# Frontboard_Rev1.net
KiCad netlist of a schematic drawn in EAGLE
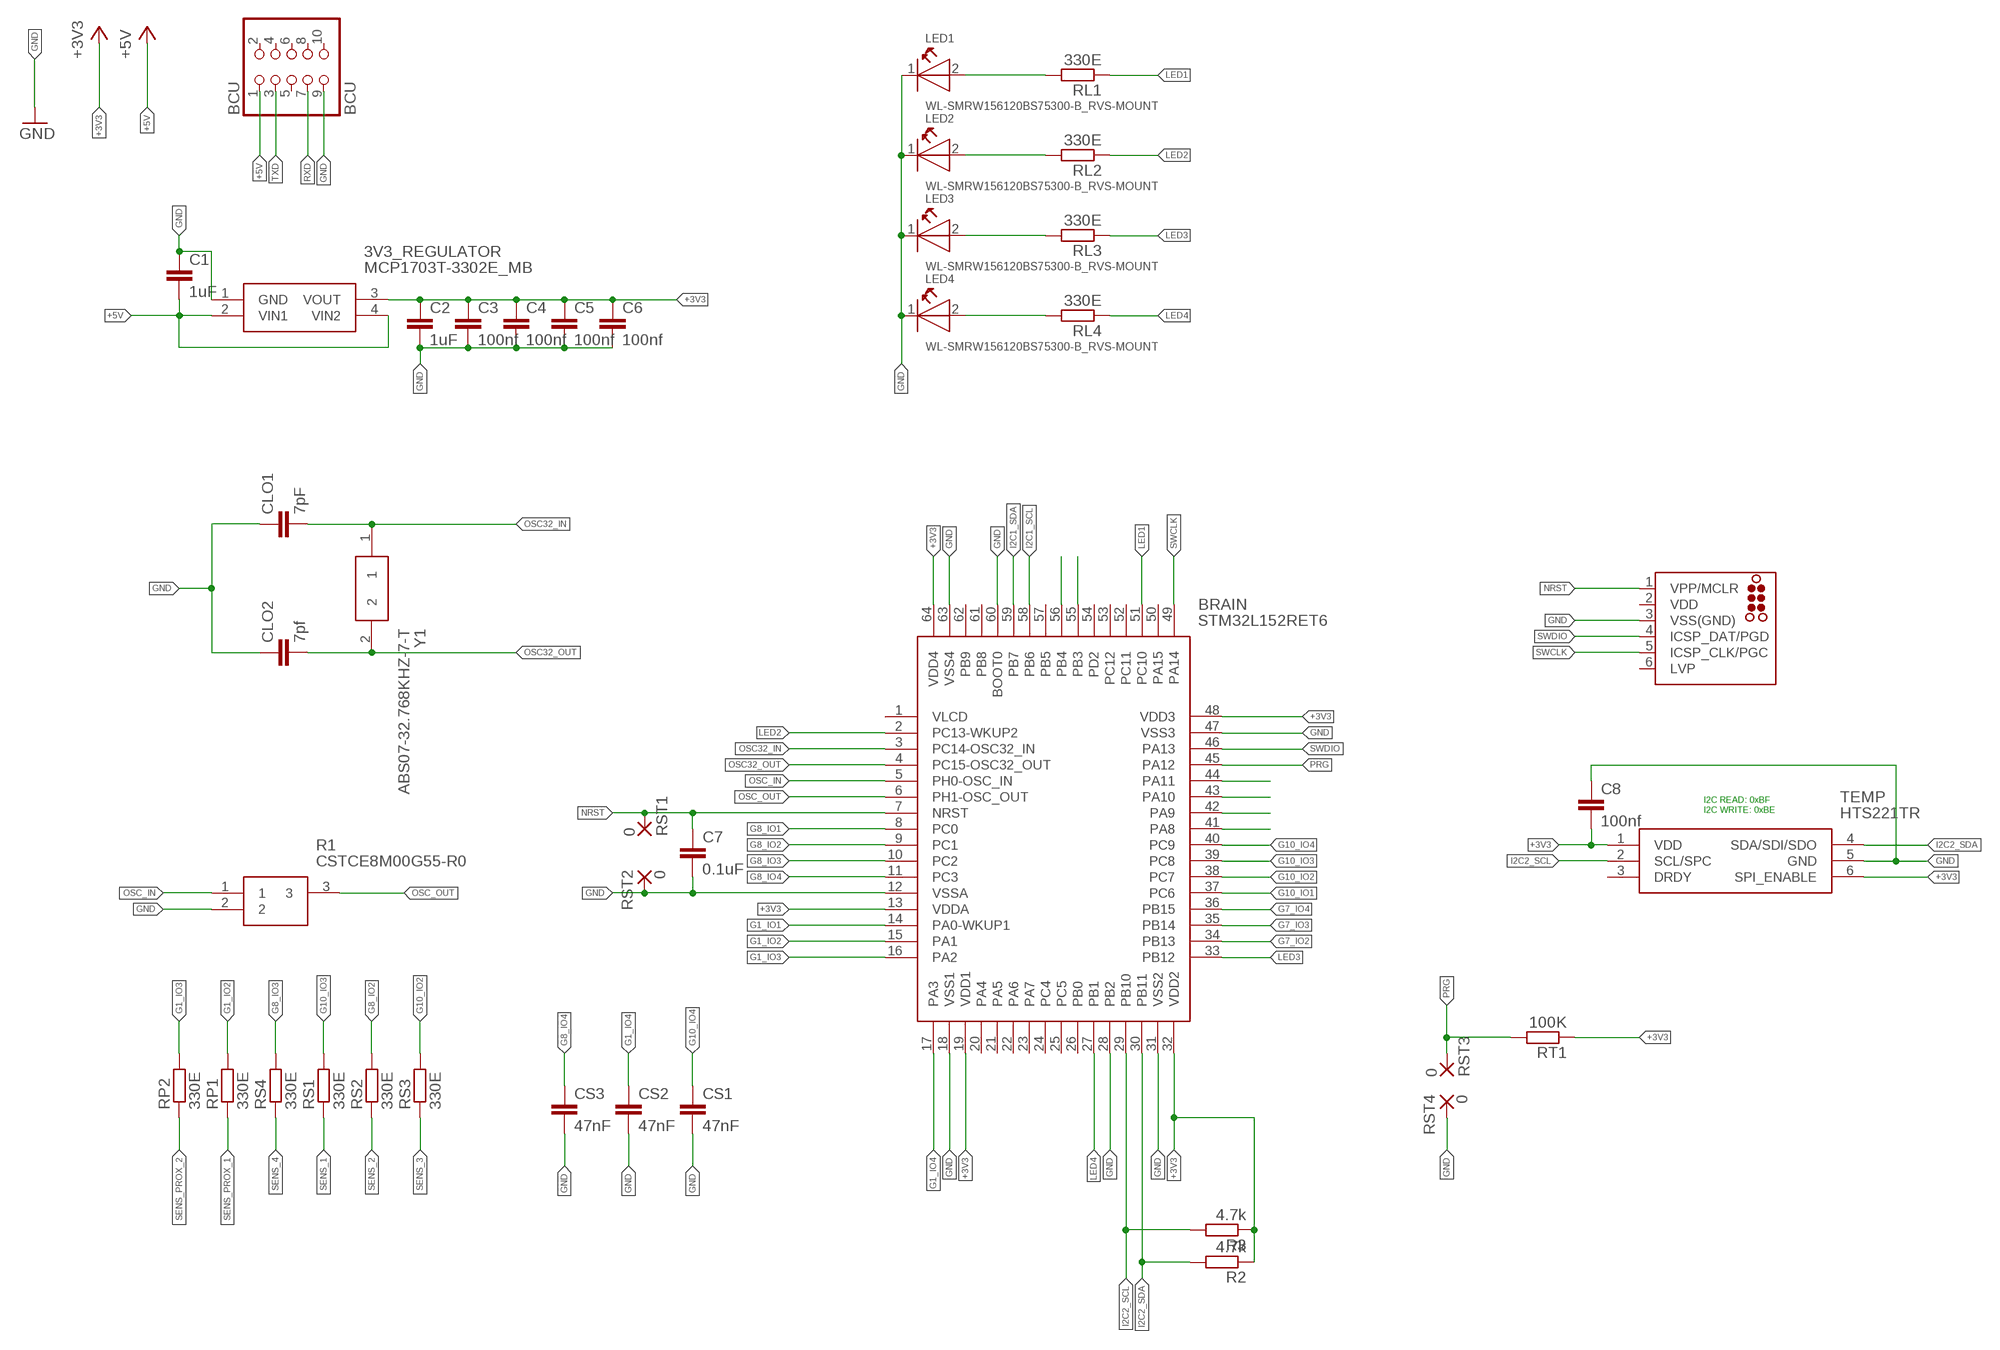
[diagram p0: schematic, sheet 1]

(export (version "E")
  (design (tool "Eeschema 10.0.6"))
  (components
    (comp (ref "3V3_REGULATOR")
      (value "MCP1703T-3302E_MB")
      (footprint "eagle-import:SOT-89(MB)")
      (fields
        (field (name "ARROW_PART_NUMBER") "MCP1703T-3302E/MB")
        (field (name "RS_PART_NUMBER") "9122916")
      )
      (libsource (lib "eagle-import") (part "MCP1703T-3302E_MB"))
    )
    (comp (ref "BCU")
      (value "BCU")
      (footprint "eagle-import:2X05SMD")
      (libsource (lib "eagle-import") (part "PINHD-2X5_2.54-SMD"))
    )
    (comp (ref "BRAIN")
      (value "STM32L152RET6")
      (footprint "eagle-import:QFP50P1200X1200X160-64N")
      (libsource (lib "eagle-import") (part "STM32L152RET6"))
    )
    (comp (ref "C1")
      (value "1uF")
      (footprint "eagle-import:C0603")
      (libsource (lib "eagle-import") (part "C-EUC0603"))
    )
    (comp (ref "C2")
      (value "1uF")
      (footprint "eagle-import:C0603")
      (libsource (lib "eagle-import") (part "C-EUC0603"))
    )
    (comp (ref "C3")
      (value "100nf")
      (footprint "eagle-import:C0603")
      (libsource (lib "eagle-import") (part "C-EUC0603"))
    )
    (comp (ref "C4")
      (value "100nf")
      (footprint "eagle-import:C0603")
      (libsource (lib "eagle-import") (part "C-EUC0603"))
    )
    (comp (ref "C5")
      (value "100nf")
      (footprint "eagle-import:C0603")
      (libsource (lib "eagle-import") (part "C-EUC0603"))
    )
    (comp (ref "C6")
      (value "100nf")
      (footprint "eagle-import:C0603")
      (libsource (lib "eagle-import") (part "C-EUC0603"))
    )
    (comp (ref "C7")
      (value "0.1uF")
      (footprint "eagle-import:C0603")
      (libsource (lib "eagle-import") (part "C-EUC0603"))
    )
    (comp (ref "C8")
      (value "100nf")
      (footprint "eagle-import:C0603")
      (libsource (lib "eagle-import") (part "C-EUC0603"))
    )
    (comp (ref "CLO1")
      (value "7pF")
      (footprint "eagle-import:C0603")
      (libsource (lib "eagle-import") (part "C-EUC0603"))
    )
    (comp (ref "CLO2")
      (value "7pf")
      (footprint "eagle-import:C0603")
      (libsource (lib "eagle-import") (part "C-EUC0603"))
    )
    (comp (ref "CS1")
      (value "47nF")
      (footprint "eagle-import:C0603")
      (libsource (lib "eagle-import") (part "C-EUC0603"))
    )
    (comp (ref "CS2")
      (value "47nF")
      (footprint "eagle-import:C0603")
      (libsource (lib "eagle-import") (part "C-EUC0603"))
    )
    (comp (ref "CS3")
      (value "47nF")
      (footprint "eagle-import:C0603")
      (libsource (lib "eagle-import") (part "C-EUC0603"))
    )
    (comp (ref "LED1")
      (value "WL-SMRW156120BS75300-B_RVS-MOUNT")
      (footprint "eagle-import:WL-SMRW-1206-CYLDR-REVERSE-MOUNT")
      (libsource (lib "eagle-import") (part "WL-SMRW156120BS75300-B_RVS-MOUNT"))
    )
    (comp (ref "LED2")
      (value "WL-SMRW156120BS75300-B_RVS-MOUNT")
      (footprint "eagle-import:WL-SMRW-1206-CYLDR-REVERSE-MOUNT")
      (libsource (lib "eagle-import") (part "WL-SMRW156120BS75300-B_RVS-MOUNT"))
    )
    (comp (ref "LED3")
      (value "WL-SMRW156120BS75300-B_RVS-MOUNT")
      (footprint "eagle-import:WL-SMRW-1206-CYLDR-REVERSE-MOUNT")
      (libsource (lib "eagle-import") (part "WL-SMRW156120BS75300-B_RVS-MOUNT"))
    )
    (comp (ref "LED4")
      (value "WL-SMRW156120BS75300-B_RVS-MOUNT")
      (footprint "eagle-import:WL-SMRW-1206-CYLDR-REVERSE-MOUNT")
      (libsource (lib "eagle-import") (part "WL-SMRW156120BS75300-B_RVS-MOUNT"))
    )
    (comp (ref "R1")
      (value "CSTCE8M00G55-R0")
      (footprint "eagle-import:CSTCE12M0G55-R0")
      (fields (field (name "RS_PART_NUMBER") "7214821P"))
      (libsource (lib "eagle-import") (part "CSTCE8M00G55-R0"))
    )
    (comp (ref "R2")
      (value "4.7k")
      (footprint "eagle-import:R0603")
      (libsource (lib "eagle-import") (part "R-EU_R0603"))
    )
    (comp (ref "R3")
      (value "4.7k")
      (footprint "eagle-import:R0603")
      (libsource (lib "eagle-import") (part "R-EU_R0603"))
    )
    (comp (ref "RL1")
      (value "330E")
      (footprint "eagle-import:R0603")
      (libsource (lib "eagle-import") (part "R-EU_R0603"))
    )
    (comp (ref "RL2")
      (value "330E")
      (footprint "eagle-import:R0603")
      (libsource (lib "eagle-import") (part "R-EU_R0603"))
    )
    (comp (ref "RL3")
      (value "330E")
      (footprint "eagle-import:R0603")
      (libsource (lib "eagle-import") (part "R-EU_R0603"))
    )
    (comp (ref "RL4")
      (value "330E")
      (footprint "eagle-import:R0603")
      (libsource (lib "eagle-import") (part "R-EU_R0603"))
    )
    (comp (ref "RP1")
      (value "330E")
      (footprint "eagle-import:R0603")
      (libsource (lib "eagle-import") (part "R-EU_R0603"))
    )
    (comp (ref "RP2")
      (value "330E")
      (footprint "eagle-import:R0603")
      (libsource (lib "eagle-import") (part "R-EU_R0603"))
    )
    (comp (ref "RS1")
      (value "330E")
      (footprint "eagle-import:R0603")
      (libsource (lib "eagle-import") (part "R-EU_R0603"))
    )
    (comp (ref "RS2")
      (value "330E")
      (footprint "eagle-import:R0603")
      (libsource (lib "eagle-import") (part "R-EU_R0603"))
    )
    (comp (ref "RS3")
      (value "330E")
      (footprint "eagle-import:R0603")
      (libsource (lib "eagle-import") (part "R-EU_R0603"))
    )
    (comp (ref "RS4")
      (value "330E")
      (footprint "eagle-import:R0603")
      (libsource (lib "eagle-import") (part "R-EU_R0603"))
    )
    (comp (ref "RST1")
      (value "0")
      (footprint "eagle-import:SMD2,54-5,08")
      (libsource (lib "eagle-import") (part "SMD5"))
    )
    (comp (ref "RST2")
      (value "0")
      (footprint "eagle-import:SMD2,54-5,08")
      (libsource (lib "eagle-import") (part "SMD5"))
    )
    (comp (ref "RST3")
      (value "0")
      (footprint "eagle-import:SMD2,54-5,08")
      (libsource (lib "eagle-import") (part "SMD5"))
    )
    (comp (ref "RST4")
      (value "0")
      (footprint "eagle-import:SMD2,54-5,08")
      (libsource (lib "eagle-import") (part "SMD5"))
    )
    (comp (ref "RT1")
      (value "100K")
      (footprint "eagle-import:R0603")
      (libsource (lib "eagle-import") (part "R-EU_R0603"))
    )
    (comp (ref "SWD")
      (value "SWD")
      (footprint "eagle-import:TC2030-MCP-NL")
      (libsource (lib "eagle-import") (part "TC2030-MCP-NL"))
    )
    (comp (ref "TEMP")
      (value "HTS221TR")
      (footprint "eagle-import:HLGA-6L")
      (fields (field (name "RS_PART_NUMBER") "1660935"))
      (libsource (lib "eagle-import") (part "HTS221TR"))
    )
    (comp (ref "Y1")
      (value "ABS07-32.768KHZ-7-T")
      (footprint "eagle-import:ABS-07")
      (fields (field (name "RS_PART_NUMBER") "1712773P"))
      (libsource (lib "eagle-import") (part "ABS07-32.768KHZ-7-T"))
    )
  )
  (nets
    (net (code "1") (name "+3V3") (class "Default")
      (node (ref "3V3_REGULATOR") (pin "3") (pinfunction "VOUT_3") (pintype "bidirectional"))
      (node (ref "BRAIN") (pin "13") (pinfunction "VDDA_13") (pintype "power_in"))
      (node (ref "BRAIN") (pin "19") (pinfunction "VDD1_19") (pintype "power_in"))
      (node (ref "BRAIN") (pin "32") (pinfunction "VDD2_32") (pintype "power_in"))
      (node (ref "BRAIN") (pin "48") (pinfunction "VDD3_48") (pintype "power_in"))
      (node (ref "BRAIN") (pin "64") (pinfunction "VDD4_64") (pintype "power_in"))
      (node (ref "C2") (pin "1") (pinfunction "1_1") (pintype "passive"))
      (node (ref "C3") (pin "1") (pinfunction "1_1") (pintype "passive"))
      (node (ref "C4") (pin "1") (pinfunction "1_1") (pintype "passive"))
      (node (ref "C5") (pin "1") (pinfunction "1_1") (pintype "passive"))
      (node (ref "C6") (pin "1") (pinfunction "1_1") (pintype "passive"))
      (node (ref "C8") (pin "2") (pinfunction "2_2") (pintype "passive"))
      (node (ref "R2") (pin "1") (pinfunction "1_1") (pintype "passive"))
      (node (ref "R3") (pin "1") (pinfunction "1_1") (pintype "passive"))
      (node (ref "RT1") (pin "1") (pinfunction "1_1") (pintype "passive"))
      (node (ref "TEMP") (pin "1") (pinfunction "VDD_1") (pintype "bidirectional"))
      (node (ref "TEMP") (pin "6") (pinfunction "SPI_ENABLE_6") (pintype "bidirectional"))
    )
    (net (code "2") (name "+5V") (class "Default")
      (node (ref "3V3_REGULATOR") (pin "2") (pinfunction "VIN1_2") (pintype "bidirectional"))
      (node (ref "3V3_REGULATOR") (pin "4") (pinfunction "VIN2_4") (pintype "bidirectional"))
      (node (ref "BCU") (pin "1") (pinfunction "1_1") (pintype "passive"))
      (node (ref "C1") (pin "2") (pinfunction "2_2") (pintype "passive"))
    )
    (net (code "3") (name "/VDD") (class "Default")
      (node (ref "SWD") (pin "2") (pinfunction "VDD_2") (pintype "power_in"))
    )
    (net (code "4") (name "/VLCD") (class "Default")
      (node (ref "BRAIN") (pin "1") (pinfunction "VLCD_1") (pintype "power_in"))
    )
    (net (code "5") (name "G1_IO1") (class "Default")
      (node (ref "BRAIN") (pin "14") (pinfunction "PA0-WKUP1_14") (pintype "bidirectional"))
    )
    (net (code "6") (name "G1_IO2") (class "Default")
      (node (ref "BRAIN") (pin "15") (pinfunction "PA1_15") (pintype "bidirectional"))
      (node (ref "RP1") (pin "2") (pinfunction "2_2") (pintype "passive"))
    )
    (net (code "7") (name "G1_IO3") (class "Default")
      (node (ref "BRAIN") (pin "16") (pinfunction "PA2_16") (pintype "bidirectional"))
      (node (ref "RP2") (pin "2") (pinfunction "2_2") (pintype "passive"))
    )
    (net (code "8") (name "G1_IO4") (class "Default")
      (node (ref "BRAIN") (pin "17") (pinfunction "PA3_17") (pintype "bidirectional"))
      (node (ref "CS2") (pin "1") (pinfunction "1_1") (pintype "passive"))
    )
    (net (code "9") (name "G7_IO2") (class "Default")
      (node (ref "BRAIN") (pin "34") (pinfunction "PB13_34") (pintype "bidirectional"))
    )
    (net (code "10") (name "G7_IO3") (class "Default")
      (node (ref "BRAIN") (pin "35") (pinfunction "PB14_35") (pintype "bidirectional"))
    )
    (net (code "11") (name "G7_IO4") (class "Default")
      (node (ref "BRAIN") (pin "36") (pinfunction "PB15_36") (pintype "bidirectional"))
    )
    (net (code "12") (name "G8_IO1") (class "Default")
      (node (ref "BRAIN") (pin "8") (pinfunction "PC0_8") (pintype "bidirectional"))
    )
    (net (code "13") (name "G8_IO2") (class "Default")
      (node (ref "BRAIN") (pin "9") (pinfunction "PC1_9") (pintype "bidirectional"))
      (node (ref "RS2") (pin "2") (pinfunction "2_2") (pintype "passive"))
    )
    (net (code "14") (name "G8_IO3") (class "Default")
      (node (ref "BRAIN") (pin "10") (pinfunction "PC2_10") (pintype "bidirectional"))
      (node (ref "RS4") (pin "2") (pinfunction "2_2") (pintype "passive"))
    )
    (net (code "15") (name "G8_IO4") (class "Default")
      (node (ref "BRAIN") (pin "11") (pinfunction "PC3_11") (pintype "bidirectional"))
      (node (ref "CS3") (pin "1") (pinfunction "1_1") (pintype "passive"))
    )
    (net (code "16") (name "G10_IO1") (class "Default")
      (node (ref "BRAIN") (pin "37") (pinfunction "PC6_37") (pintype "bidirectional"))
    )
    (net (code "17") (name "G10_IO2") (class "Default")
      (node (ref "BRAIN") (pin "38") (pinfunction "PC7_38") (pintype "bidirectional"))
      (node (ref "RS3") (pin "2") (pinfunction "2_2") (pintype "passive"))
    )
    (net (code "18") (name "G10_IO3") (class "Default")
      (node (ref "BRAIN") (pin "39") (pinfunction "PC8_39") (pintype "bidirectional"))
      (node (ref "RS1") (pin "2") (pinfunction "2_2") (pintype "passive"))
    )
    (net (code "19") (name "G10_IO4") (class "Default")
      (node (ref "BRAIN") (pin "40") (pinfunction "PC9_40") (pintype "bidirectional"))
      (node (ref "CS1") (pin "1") (pinfunction "1_1") (pintype "passive"))
    )
    (net (code "20") (name "GND") (class "Default")
      (node (ref "3V3_REGULATOR") (pin "1") (pinfunction "GND_1") (pintype "bidirectional"))
      (node (ref "BCU") (pin "9") (pinfunction "9_9") (pintype "passive"))
      (node (ref "BRAIN") (pin "12") (pinfunction "VSSA_12") (pintype "power_in"))
      (node (ref "BRAIN") (pin "18") (pinfunction "VSS1_18") (pintype "power_in"))
      (node (ref "BRAIN") (pin "28") (pinfunction "PB2_28") (pintype "bidirectional"))
      (node (ref "BRAIN") (pin "31") (pinfunction "VSS2_31") (pintype "power_in"))
      (node (ref "BRAIN") (pin "47") (pinfunction "VSS3_47") (pintype "power_in"))
      (node (ref "BRAIN") (pin "60") (pinfunction "BOOT0_60") (pintype "bidirectional"))
      (node (ref "BRAIN") (pin "63") (pinfunction "VSS4_63") (pintype "power_in"))
      (node (ref "C1") (pin "1") (pinfunction "1_1") (pintype "passive"))
      (node (ref "C2") (pin "2") (pinfunction "2_2") (pintype "passive"))
      (node (ref "C3") (pin "2") (pinfunction "2_2") (pintype "passive"))
      (node (ref "C4") (pin "2") (pinfunction "2_2") (pintype "passive"))
      (node (ref "C5") (pin "2") (pinfunction "2_2") (pintype "passive"))
      (node (ref "C6") (pin "2") (pinfunction "2_2") (pintype "passive"))
      (node (ref "C7") (pin "2") (pinfunction "2_2") (pintype "passive"))
      (node (ref "C8") (pin "1") (pinfunction "1_1") (pintype "passive"))
      (node (ref "CLO1") (pin "1") (pinfunction "1_1") (pintype "passive"))
      (node (ref "CLO2") (pin "1") (pinfunction "1_1") (pintype "passive"))
      (node (ref "CS1") (pin "2") (pinfunction "2_2") (pintype "passive"))
      (node (ref "CS2") (pin "2") (pinfunction "2_2") (pintype "passive"))
      (node (ref "CS3") (pin "2") (pinfunction "2_2") (pintype "passive"))
      (node (ref "LED1") (pin "1") (pinfunction "K_1") (pintype "bidirectional"))
      (node (ref "LED2") (pin "1") (pinfunction "K_1") (pintype "bidirectional"))
      (node (ref "LED3") (pin "1") (pinfunction "K_1") (pintype "bidirectional"))
      (node (ref "LED4") (pin "1") (pinfunction "K_1") (pintype "bidirectional"))
      (node (ref "R1") (pin "2") (pinfunction "2_2") (pintype "bidirectional"))
      (node (ref "RST2") (pin "1") (pinfunction "P_1") (pintype "passive"))
      (node (ref "RST4") (pin "1") (pinfunction "P_1") (pintype "passive"))
      (node (ref "SWD") (pin "3") (pinfunction "VSS(GND)_3") (pintype "power_in"))
      (node (ref "TEMP") (pin "5") (pinfunction "GND_5") (pintype "bidirectional"))
    )
    (net (code "21") (name "I2C1_SCL") (class "Default")
      (node (ref "BRAIN") (pin "58") (pinfunction "PB6_58") (pintype "bidirectional"))
    )
    (net (code "22") (name "I2C1_SDA") (class "Default")
      (node (ref "BRAIN") (pin "59") (pinfunction "PB7_59") (pintype "bidirectional"))
    )
    (net (code "23") (name "I2C2_SCL") (class "Default")
      (node (ref "BRAIN") (pin "29") (pinfunction "PB10_29") (pintype "bidirectional"))
      (node (ref "R3") (pin "2") (pinfunction "2_2") (pintype "passive"))
      (node (ref "TEMP") (pin "2") (pinfunction "SCL/SPC_2") (pintype "bidirectional"))
    )
    (net (code "24") (name "I2C2_SDA") (class "Default")
      (node (ref "BRAIN") (pin "30") (pinfunction "PB11_30") (pintype "bidirectional"))
      (node (ref "R2") (pin "2") (pinfunction "2_2") (pintype "passive"))
      (node (ref "TEMP") (pin "4") (pinfunction "SDA/SDI/SDO_4") (pintype "bidirectional"))
    )
    (net (code "25") (name "LED1") (class "Default")
      (node (ref "BRAIN") (pin "51") (pinfunction "PC10_51") (pintype "bidirectional"))
      (node (ref "RL1") (pin "1") (pinfunction "1_1") (pintype "passive"))
    )
    (net (code "26") (name "LED2") (class "Default")
      (node (ref "BRAIN") (pin "2") (pinfunction "PC13-WKUP2_2") (pintype "bidirectional"))
      (node (ref "RL2") (pin "1") (pinfunction "1_1") (pintype "passive"))
    )
    (net (code "27") (name "LED3") (class "Default")
      (node (ref "BRAIN") (pin "33") (pinfunction "PB12_33") (pintype "bidirectional"))
      (node (ref "RL3") (pin "1") (pinfunction "1_1") (pintype "passive"))
    )
    (net (code "28") (name "LED4") (class "Default")
      (node (ref "BRAIN") (pin "27") (pinfunction "PB1_27") (pintype "bidirectional"))
      (node (ref "RL4") (pin "1") (pinfunction "1_1") (pintype "passive"))
    )
    (net (code "29") (name "NRST") (class "Default")
      (node (ref "BRAIN") (pin "7") (pinfunction "NRST_7") (pintype "bidirectional"))
      (node (ref "C7") (pin "1") (pinfunction "1_1") (pintype "passive"))
      (node (ref "RST1") (pin "1") (pinfunction "P_1") (pintype "passive"))
      (node (ref "SWD") (pin "1") (pinfunction "VPP/MCLR_1") (pintype "passive"))
    )
    (net (code "30") (name "Net-(LED1-A)") (class "Default")
      (node (ref "LED1") (pin "2") (pinfunction "A_2") (pintype "bidirectional"))
      (node (ref "RL1") (pin "2") (pinfunction "2_2") (pintype "passive"))
    )
    (net (code "31") (name "Net-(LED2-A)") (class "Default")
      (node (ref "LED2") (pin "2") (pinfunction "A_2") (pintype "bidirectional"))
      (node (ref "RL2") (pin "2") (pinfunction "2_2") (pintype "passive"))
    )
    (net (code "32") (name "Net-(LED3-A)") (class "Default")
      (node (ref "LED3") (pin "2") (pinfunction "A_2") (pintype "bidirectional"))
      (node (ref "RL3") (pin "2") (pinfunction "2_2") (pintype "passive"))
    )
    (net (code "33") (name "Net-(LED4-A)") (class "Default")
      (node (ref "LED4") (pin "2") (pinfunction "A_2") (pintype "bidirectional"))
      (node (ref "RL4") (pin "2") (pinfunction "2_2") (pintype "passive"))
    )
    (net (code "34") (name "OSC32_IN") (class "Default")
      (node (ref "BRAIN") (pin "3") (pinfunction "PC14-OSC32_IN_3") (pintype "bidirectional"))
      (node (ref "CLO1") (pin "2") (pinfunction "2_2") (pintype "passive"))
      (node (ref "Y1") (pin "1") (pinfunction "1_1") (pintype "bidirectional"))
    )
    (net (code "35") (name "OSC32_OUT") (class "Default")
      (node (ref "BRAIN") (pin "4") (pinfunction "PC15-OSC32_OUT_4") (pintype "bidirectional"))
      (node (ref "CLO2") (pin "2") (pinfunction "2_2") (pintype "passive"))
      (node (ref "Y1") (pin "2") (pinfunction "2_2") (pintype "bidirectional"))
    )
    (net (code "36") (name "OSC_IN") (class "Default")
      (node (ref "BRAIN") (pin "5") (pinfunction "PH0-OSC_IN_5") (pintype "bidirectional"))
      (node (ref "R1") (pin "1") (pinfunction "1_1") (pintype "bidirectional"))
    )
    (net (code "37") (name "OSC_OUT") (class "Default")
      (node (ref "BRAIN") (pin "6") (pinfunction "PH1-OSC_OUT_6") (pintype "bidirectional"))
      (node (ref "R1") (pin "3") (pinfunction "3_3") (pintype "bidirectional"))
    )
    (net (code "38") (name "PRG") (class "Default")
      (node (ref "BRAIN") (pin "45") (pinfunction "PA12_45") (pintype "bidirectional"))
      (node (ref "RST3") (pin "1") (pinfunction "P_1") (pintype "passive"))
      (node (ref "RT1") (pin "2") (pinfunction "2_2") (pintype "passive"))
    )
    (net (code "39") (name "RXD") (class "Default")
      (node (ref "BCU") (pin "7") (pinfunction "7_7") (pintype "passive"))
    )
    (net (code "40") (name "SENS_1") (class "Default")
      (node (ref "RS1") (pin "1") (pinfunction "1_1") (pintype "passive"))
    )
    (net (code "41") (name "SENS_2") (class "Default")
      (node (ref "RS2") (pin "1") (pinfunction "1_1") (pintype "passive"))
    )
    (net (code "42") (name "SENS_3") (class "Default")
      (node (ref "RS3") (pin "1") (pinfunction "1_1") (pintype "passive"))
    )
    (net (code "43") (name "SENS_4") (class "Default")
      (node (ref "RS4") (pin "1") (pinfunction "1_1") (pintype "passive"))
    )
    (net (code "44") (name "SENS_PROX_1") (class "Default")
      (node (ref "RP1") (pin "1") (pinfunction "1_1") (pintype "passive"))
    )
    (net (code "45") (name "SENS_PROX_2") (class "Default")
      (node (ref "RP2") (pin "1") (pinfunction "1_1") (pintype "passive"))
    )
    (net (code "46") (name "SWCLK") (class "Default")
      (node (ref "BRAIN") (pin "49") (pinfunction "PA14_49") (pintype "bidirectional"))
      (node (ref "SWD") (pin "5") (pinfunction "ICSP_CLK/PGC_5") (pintype "output"))
    )
    (net (code "47") (name "SWDIO") (class "Default")
      (node (ref "BRAIN") (pin "46") (pinfunction "PA13_46") (pintype "bidirectional"))
      (node (ref "SWD") (pin "4") (pinfunction "ICSP_DAT/PGD_4") (pintype "bidirectional"))
    )
    (net (code "48") (name "TXD") (class "Default")
      (node (ref "BCU") (pin "3") (pinfunction "3_3") (pintype "passive"))
    )
    (net (code "49") (name "unconnected-(BCU-Pad2)") (class "Default")
      (node (ref "BCU") (pin "2") (pinfunction "2_2") (pintype "passive"))
    )
    (net (code "50") (name "unconnected-(BCU-Pad4)") (class "Default")
      (node (ref "BCU") (pin "4") (pinfunction "4_4") (pintype "passive"))
    )
    (net (code "51") (name "unconnected-(BCU-Pad5)") (class "Default")
      (node (ref "BCU") (pin "5") (pinfunction "5_5") (pintype "passive"))
    )
    (net (code "52") (name "unconnected-(BCU-Pad6)") (class "Default")
      (node (ref "BCU") (pin "6") (pinfunction "6_6") (pintype "passive"))
    )
    (net (code "53") (name "unconnected-(BCU-Pad8)") (class "Default")
      (node (ref "BCU") (pin "8") (pinfunction "8_8") (pintype "passive"))
    )
    (net (code "54") (name "unconnected-(BCU-Pad10)") (class "Default")
      (node (ref "BCU") (pin "10") (pinfunction "10_10") (pintype "passive"))
    )
    (net (code "55") (name "unconnected-(BRAIN-PA4-Pad20)") (class "Default")
      (node (ref "BRAIN") (pin "20") (pinfunction "PA4_20") (pintype "bidirectional"))
    )
    (net (code "56") (name "unconnected-(BRAIN-PA5-Pad21)") (class "Default")
      (node (ref "BRAIN") (pin "21") (pinfunction "PA5_21") (pintype "bidirectional"))
    )
    (net (code "57") (name "unconnected-(BRAIN-PA6-Pad22)") (class "Default")
      (node (ref "BRAIN") (pin "22") (pinfunction "PA6_22") (pintype "bidirectional"))
    )
    (net (code "58") (name "unconnected-(BRAIN-PA7-Pad23)") (class "Default")
      (node (ref "BRAIN") (pin "23") (pinfunction "PA7_23") (pintype "bidirectional"))
    )
    (net (code "59") (name "unconnected-(BRAIN-PA8-Pad41)") (class "Default")
      (node (ref "BRAIN") (pin "41") (pinfunction "PA8_41") (pintype "bidirectional"))
    )
    (net (code "60") (name "unconnected-(BRAIN-PA9-Pad42)") (class "Default")
      (node (ref "BRAIN") (pin "42") (pinfunction "PA9_42") (pintype "bidirectional"))
    )
    (net (code "61") (name "unconnected-(BRAIN-PA10-Pad43)") (class "Default")
      (node (ref "BRAIN") (pin "43") (pinfunction "PA10_43") (pintype "bidirectional"))
    )
    (net (code "62") (name "unconnected-(BRAIN-PA11-Pad44)") (class "Default")
      (node (ref "BRAIN") (pin "44") (pinfunction "PA11_44") (pintype "bidirectional"))
    )
    (net (code "63") (name "unconnected-(BRAIN-PA15-Pad50)") (class "Default")
      (node (ref "BRAIN") (pin "50") (pinfunction "PA15_50") (pintype "bidirectional"))
    )
    (net (code "64") (name "unconnected-(BRAIN-PB0-Pad26)") (class "Default")
      (node (ref "BRAIN") (pin "26") (pinfunction "PB0_26") (pintype "bidirectional"))
    )
    (net (code "65") (name "unconnected-(BRAIN-PB3-Pad55)") (class "Default")
      (node (ref "BRAIN") (pin "55") (pinfunction "PB3_55") (pintype "bidirectional"))
    )
    (net (code "66") (name "unconnected-(BRAIN-PB4-Pad56)") (class "Default")
      (node (ref "BRAIN") (pin "56") (pinfunction "PB4_56") (pintype "bidirectional"))
    )
    (net (code "67") (name "unconnected-(BRAIN-PB5-Pad57)") (class "Default")
      (node (ref "BRAIN") (pin "57") (pinfunction "PB5_57") (pintype "bidirectional"))
    )
    (net (code "68") (name "unconnected-(BRAIN-PB8-Pad61)") (class "Default")
      (node (ref "BRAIN") (pin "61") (pinfunction "PB8_61") (pintype "bidirectional"))
    )
    (net (code "69") (name "unconnected-(BRAIN-PB9-Pad62)") (class "Default")
      (node (ref "BRAIN") (pin "62") (pinfunction "PB9_62") (pintype "bidirectional"))
    )
    (net (code "70") (name "unconnected-(BRAIN-PC4-Pad24)") (class "Default")
      (node (ref "BRAIN") (pin "24") (pinfunction "PC4_24") (pintype "bidirectional"))
    )
    (net (code "71") (name "unconnected-(BRAIN-PC5-Pad25)") (class "Default")
      (node (ref "BRAIN") (pin "25") (pinfunction "PC5_25") (pintype "bidirectional"))
    )
    (net (code "72") (name "unconnected-(BRAIN-PC11-Pad52)") (class "Default")
      (node (ref "BRAIN") (pin "52") (pinfunction "PC11_52") (pintype "bidirectional"))
    )
    (net (code "73") (name "unconnected-(BRAIN-PC12-Pad53)") (class "Default")
      (node (ref "BRAIN") (pin "53") (pinfunction "PC12_53") (pintype "bidirectional"))
    )
    (net (code "74") (name "unconnected-(BRAIN-PD2-Pad54)") (class "Default")
      (node (ref "BRAIN") (pin "54") (pinfunction "PD2_54") (pintype "bidirectional"))
    )
    (net (code "75") (name "unconnected-(SWD-LVP-Pad6)") (class "Default")
      (node (ref "SWD") (pin "6") (pinfunction "LVP_6") (pintype "bidirectional"))
    )
    (net (code "76") (name "unconnected-(TEMP-DRDY-Pad3)") (class "Default")
      (node (ref "TEMP") (pin "3") (pinfunction "DRDY_3") (pintype "bidirectional"))
    )
  )
)
